# Main.net
KiCad netlist of a schematic drawn in Altium Designer
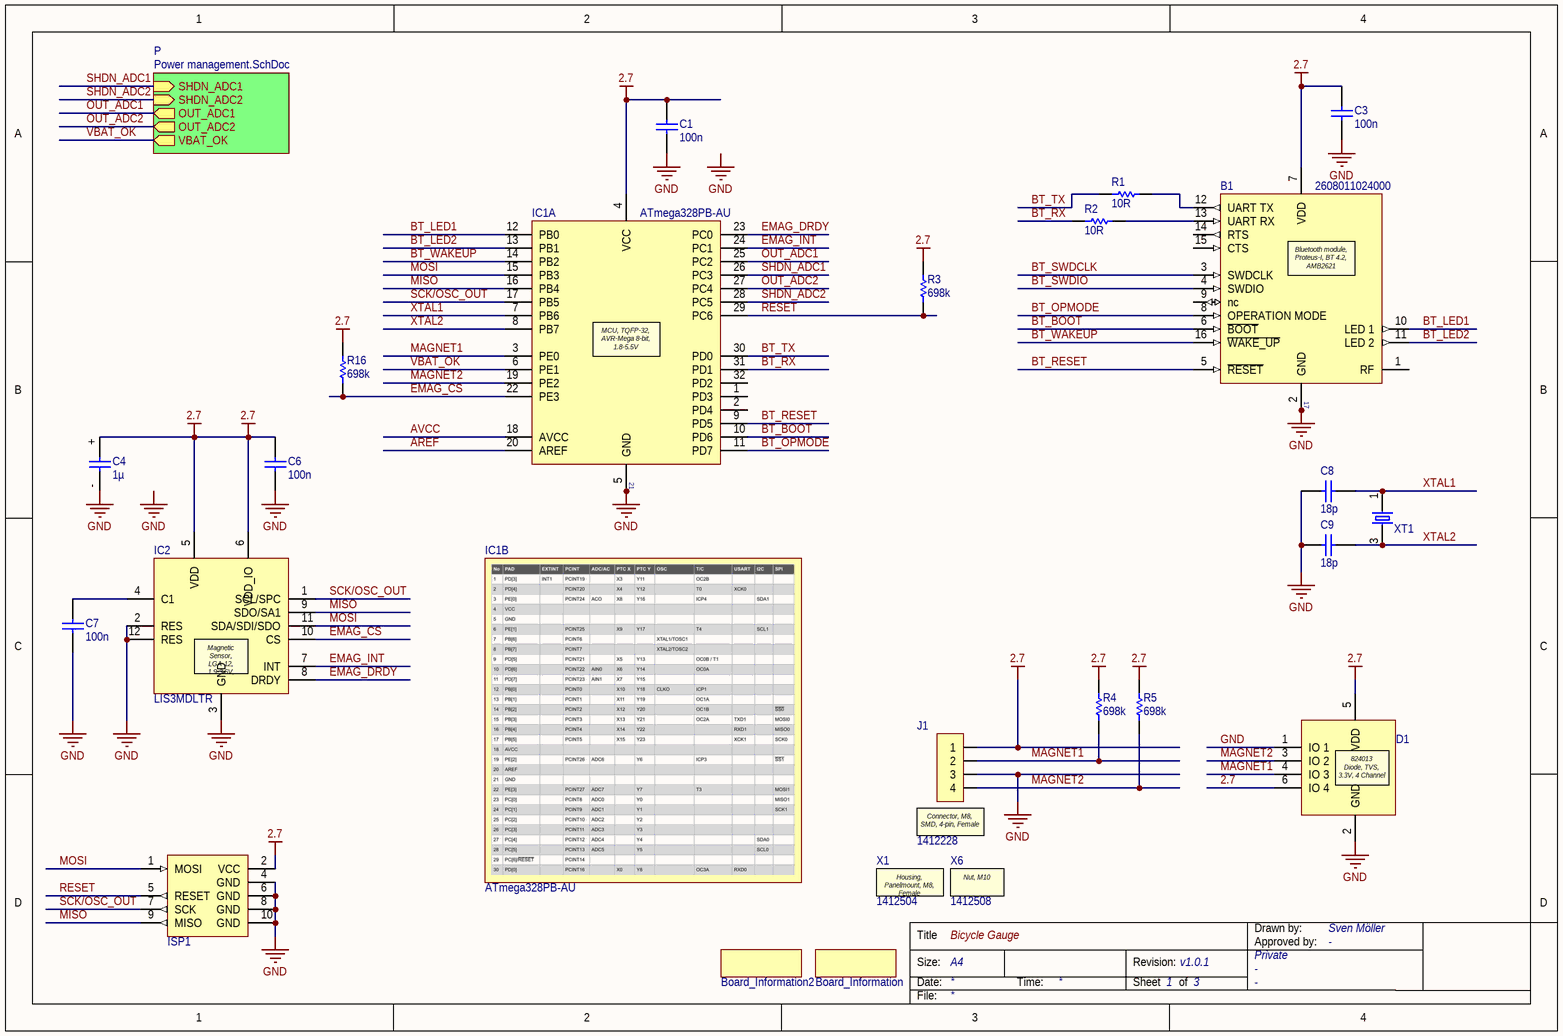
[diagram p0: Main.SchDoc]

(export (version "E")
  (design (tool "Eeschema 10.0.6"))
  (components
    (comp (ref "B1")
      (value "2608011024000")
      (footprint "AMB2621")
      (description "Bluetooth module, Proteus-I, BT 4.2, AMB2621")
      (fields (field (name "MANUFACTURER") "Würth Elektronik") (field (name "MPN") "2608011024000"))
      (libsource (lib "Schlib1") (part "2608011024000"))
    )
    (comp (ref "Board_Information")
      (value "Board_Information")
      (footprint "Board_Information")
      (description "Board Information")
      (libsource (lib "Schlib1") (part "Board_Information"))
    )
    (comp (ref "Board_Information2")
      (value "Board_Information")
      (footprint "Board_Information")
      (description "Board Information")
      (libsource (lib "Schlib1") (part "Board_Information"))
    )
    (comp (ref "C1")
      (value "100n")
      (footprint "C0603")
      (description "Cap, 100n, 0603, X7R, 50V")
      (fields (field (name "MANUFACTURER") "Yageo") (field (name "MPN") "CC0603KRX7R9BB104"))
      (libsource (lib "Createc Circuitstudio Library") (part "CC0603KRX7R9BB104"))
    )
    (comp (ref "C3")
      (value "100n")
      (footprint "C0603")
      (description "Cap, 100n, 0603, X7R, 50V")
      (fields (field (name "MANUFACTURER") "Yageo") (field (name "MPN") "CC0603KRX7R9BB104"))
      (libsource (lib "Createc Circuitstudio Library") (part "CC0603KRX7R9BB104"))
    )
    (comp (ref "C4")
      (value "1µ")
      (footprint "ELCAP_4x5.4mm")
      (description "Cap, 1µ, 4x5.4mm, Aluminum Electrolyte, 35V")
      (fields (field (name "MPN") "EEE-FC1V1R0R") (field (name "MANUFACTURER") "Panasonic"))
      (libsource (lib "Schlib1") (part "EEE-FC1V1R0R"))
    )
    (comp (ref "C6")
      (value "100n")
      (footprint "C0603")
      (description "Cap, 100n, 0603, X7R, 50V")
      (fields (field (name "MANUFACTURER") "Yageo") (field (name "MPN") "CC0603KRX7R9BB104"))
      (libsource (lib "Createc Circuitstudio Library") (part "CC0603KRX7R9BB104"))
    )
    (comp (ref "C7")
      (value "100n")
      (footprint "C0603")
      (description "Cap, 100n, 0603, X7R, 50V")
      (fields (field (name "MANUFACTURER") "Yageo") (field (name "MPN") "CC0603KRX7R9BB104"))
      (libsource (lib "Createc Circuitstudio Library") (part "CC0603KRX7R9BB104"))
    )
    (comp (ref "C8")
      (value "18p")
      (footprint "C0603")
      (description "Cap, 18p, 0603, C0G, 50V")
      (fields (field (name "MPN") "C0603C180J5GACTU") (field (name "MANUFACTURER") "Kemet"))
      (libsource (lib "Schlib1") (part "C0603C180J5GACTU"))
    )
    (comp (ref "C9")
      (value "18p")
      (footprint "C0603")
      (description "Cap, 18p, 0603, C0G, 50V")
      (fields (field (name "MPN") "C0603C180J5GACTU") (field (name "MANUFACTURER") "Kemet"))
      (libsource (lib "Schlib1") (part "C0603C180J5GACTU"))
    )
    (comp (ref "D1")
      (value "824013")
      (footprint "SOT-23-6")
      (description "Diode, TVS, 3.3V, 4 Channel")
      (fields (field (name "MANUFACTURER") "Würth Electronics"))
      (libsource (lib "Createc Circuitstudio Library") (part "824013"))
    )
    (comp (ref "IC1")
      (value "ATmega328PB-AU")
      (footprint "TQFP-32")
      (description "MCU, TQFP-32, AVR-Mega 8-bit, 1.8-5.5V")
      (fields (field (name "MANUFACTURER") "Microchip") (field (name "MPN") "ATmega328PB-AU"))
      (libsource (lib "Schlib1") (part "ATmega328PB-AU"))
    )
    (comp (ref "IC2")
      (value "LIS3MDLTR")
      (footprint "LGA-12")
      (description "Magnetic Sensor, LGA-12, 1.9-3.6V, +/-1.6mT")
      (fields (field (name "MANUFACTURER") "ST Microelectronics") (field (name "MPN") "LIS3MDLTR"))
      (libsource (lib "Schlib1") (part "LIS3MDLTR"))
    )
    (comp (ref "ISP1")
      (value "TC2050-IDC-NL")
      (footprint "TC2050-IDC-NL")
      (libsource (lib "Createc Circuitstudio Library") (part "TC2050-IDC-NL"))
    )
    (comp (ref "J1")
      (value "1412228")
      (footprint "1412228")
      (description "Connector, M8, SMD, 4-pin, Female")
      (fields (field (name "MANUFACTURER") "Phoenix Contact") (field (name "MPN") "1412228"))
      (libsource (lib "Schlib1") (part "1412228"))
    )
    (comp (ref "R1")
      (value "10R")
      (footprint "R0603")
      (description "Res, 10R, 0603, 1%, 100mW, 50V")
      (fields (field (name "TOLERANCE") "1%") (field (name "MPN") "ERJ-3EKF10R0V"))
      (libsource (lib "Createc Circuitstudio Library") (part "ERJ-3EKF10R0V"))
    )
    (comp (ref "R2")
      (value "10R")
      (footprint "R0603")
      (description "Res, 10R, 0603, 1%, 100mW, 50V")
      (fields (field (name "TOLERANCE") "1%") (field (name "MPN") "ERJ-3EKF10R0V"))
      (libsource (lib "Createc Circuitstudio Library") (part "ERJ-3EKF10R0V"))
    )
    (comp (ref "R3")
      (value "698k")
      (footprint "R0603")
      (description "Res, 698k, 0603, 1%, 75V, 100mW")
      (fields (field (name "TOLERANCE") "1%") (field (name "MPN") "ERJ-3EKF6983V"))
      (libsource (lib "Schlib1") (part "ERJ-3EKF6983V"))
    )
    (comp (ref "R4")
      (value "698k")
      (footprint "R0603")
      (description "Res, 698k, 0603, 1%, 75V, 100mW")
      (fields (field (name "TOLERANCE") "1%") (field (name "MPN") "ERJ-3EKF6983V"))
      (libsource (lib "Schlib1") (part "ERJ-3EKF6983V"))
    )
    (comp (ref "R5")
      (value "698k")
      (footprint "R0603")
      (description "Res, 698k, 0603, 1%, 75V, 100mW")
      (fields (field (name "TOLERANCE") "1%") (field (name "MPN") "ERJ-3EKF6983V"))
      (libsource (lib "Schlib1") (part "ERJ-3EKF6983V"))
    )
    (comp (ref "R16")
      (value "698k")
      (footprint "R0603")
      (description "Res, 698k, 0603, 1%, 75V, 100mW")
      (fields (field (name "TOLERANCE") "1%") (field (name "MPN") "ERJ-3EKF6983V"))
      (libsource (lib "Schlib1") (part "ERJ-3EKF6983V"))
    )
    (comp (ref "X1")
      (value "1412504")
      (footprint "1412504")
      (description "Housing, Panelmount, M8, Female")
      (fields (field (name "MANUFACTURER") "Phoenix Contact") (field (name "MPN") "1412504"))
      (libsource (lib "Schlib1") (part "1412504"))
    )
    (comp (ref "X6")
      (value "1412508")
      (footprint "1412508")
      (description "Nut, M10")
      (fields (field (name "MANUFACTURER") "Phoenix Contact") (field (name "MPN") "1412508"))
      (libsource (lib "Schlib1") (part "1412508"))
    )
    (comp (ref "XT1")
      (value "ABMM2-7.3728MHZ-E2-T")
      (footprint "Crystal_6x3.6mm")
      (description "Crystal, SMD, 7.3728MHz, 18pF")
      (fields (field (name "MANUFACTURER") "Abracon"))
      (libsource (lib "Schlib1") (part "ABMM2-7.3728MHZ-E2-T"))
    )
  )
  (nets
    (net (code "1") (name "/AREF") (class "Default")
      (node (ref "IC1") (pin "20") (pinfunction "AREF_20") (pintype "passive"))
    )
    (net (code "2") (name "/AVCC") (class "Default")
      (node (ref "IC1") (pin "18") (pinfunction "AVCC_18") (pintype "passive"))
    )
    (net (code "3") (name "/BT_BOOT") (class "Default")
      (node (ref "B1") (pin "6") (pinfunction "~{BOOT}_6") (pintype "input"))
      (node (ref "IC1") (pin "10") (pinfunction "PD6_10") (pintype "passive"))
    )
    (net (code "4") (name "/BT_LED1") (class "Default")
      (node (ref "B1") (pin "10") (pinfunction "LED_1_10") (pintype "output"))
      (node (ref "IC1") (pin "12") (pinfunction "PB0_12") (pintype "passive"))
    )
    (net (code "5") (name "/BT_LED2") (class "Default")
      (node (ref "B1") (pin "11") (pinfunction "LED_2_11") (pintype "output"))
      (node (ref "IC1") (pin "13") (pinfunction "PB1_13") (pintype "passive"))
    )
    (net (code "6") (name "/BT_OPMODE") (class "Default")
      (node (ref "B1") (pin "8") (pinfunction "OPERATION_MODE_8") (pintype "input"))
      (node (ref "IC1") (pin "11") (pinfunction "PD7_11") (pintype "passive"))
    )
    (net (code "7") (name "/BT_RESET") (class "Default")
      (node (ref "B1") (pin "5") (pinfunction "~{RESET}_5") (pintype "input"))
      (node (ref "IC1") (pin "9") (pinfunction "PD5_9") (pintype "passive"))
    )
    (net (code "8") (name "/BT_RX") (class "Default")
      (node (ref "IC1") (pin "31") (pinfunction "PD1_31") (pintype "passive"))
      (node (ref "R2") (pin "1") (pinfunction "1_1") (pintype "passive"))
    )
    (net (code "9") (name "/BT_SWDCLK") (class "Default")
      (node (ref "B1") (pin "3") (pinfunction "SWDCLK_3") (pintype "input"))
    )
    (net (code "10") (name "/BT_SWDIO") (class "Default")
      (node (ref "B1") (pin "4") (pinfunction "SWDIO_4") (pintype "input"))
    )
    (net (code "11") (name "/BT_TX") (class "Default")
      (node (ref "IC1") (pin "30") (pinfunction "PD0_30") (pintype "passive"))
      (node (ref "R1") (pin "1") (pinfunction "1_1") (pintype "passive"))
    )
    (net (code "12") (name "/BT_WAKEUP") (class "Default")
      (node (ref "B1") (pin "16") (pinfunction "~{WAKE_UP}_16") (pintype "input"))
      (node (ref "IC1") (pin "14") (pinfunction "PB2_14") (pintype "passive"))
    )
    (net (code "13") (name "/EMAG_CS") (class "Default")
      (node (ref "IC1") (pin "22") (pinfunction "PE3_22") (pintype "passive"))
      (node (ref "IC2") (pin "10") (pinfunction "CS_10") (pintype "passive"))
      (node (ref "R16") (pin "1") (pinfunction "1_1") (pintype "passive"))
    )
    (net (code "14") (name "/EMAG_DRDY") (class "Default")
      (node (ref "IC1") (pin "23") (pinfunction "PC0_23") (pintype "passive"))
      (node (ref "IC2") (pin "8") (pinfunction "DRDY_8") (pintype "passive"))
    )
    (net (code "15") (name "/EMAG_INT") (class "Default")
      (node (ref "IC1") (pin "24") (pinfunction "PC1_24") (pintype "passive"))
      (node (ref "IC2") (pin "7") (pinfunction "INT_7") (pintype "passive"))
    )
    (net (code "16") (name "/MAGNET1") (class "Default")
      (node (ref "D1") (pin "4") (pinfunction "IO_3_4") (pintype "passive"))
      (node (ref "IC1") (pin "3") (pinfunction "PE0_3") (pintype "passive"))
      (node (ref "J1") (pin "2") (pinfunction "2_2") (pintype "passive"))
      (node (ref "R4") (pin "1") (pinfunction "1_1") (pintype "passive"))
    )
    (net (code "17") (name "/MAGNET2") (class "Default")
      (node (ref "D1") (pin "3") (pinfunction "IO_2_3") (pintype "passive"))
      (node (ref "IC1") (pin "19") (pinfunction "PE2_19") (pintype "passive"))
      (node (ref "J1") (pin "4") (pinfunction "4_4") (pintype "passive"))
      (node (ref "R5") (pin "1") (pinfunction "1_1") (pintype "passive"))
    )
    (net (code "18") (name "/MISO") (class "Default")
      (node (ref "IC1") (pin "16") (pinfunction "PB4_16") (pintype "passive"))
      (node (ref "IC2") (pin "9") (pinfunction "SDO/SA1_9") (pintype "passive"))
      (node (ref "ISP1") (pin "9") (pinfunction "MISO_9") (pintype "output"))
    )
    (net (code "19") (name "/MOSI") (class "Default")
      (node (ref "IC1") (pin "15") (pinfunction "PB3_15") (pintype "passive"))
      (node (ref "IC2") (pin "11") (pinfunction "SDA/SDI/SDO_11") (pintype "passive"))
      (node (ref "ISP1") (pin "1") (pinfunction "MOSI_1") (pintype "input"))
    )
    (net (code "20") (name "/OUT_ADC1") (class "Default")
      (node (ref "IC1") (pin "25") (pinfunction "PC2_25") (pintype "passive"))
    )
    (net (code "21") (name "/OUT_ADC2") (class "Default")
      (node (ref "IC1") (pin "27") (pinfunction "PC4_27") (pintype "passive"))
    )
    (net (code "22") (name "/RESET") (class "Default")
      (node (ref "IC1") (pin "29") (pinfunction "PC6_29") (pintype "passive"))
      (node (ref "ISP1") (pin "5") (pinfunction "RESET_5") (pintype "output"))
      (node (ref "R3") (pin "1") (pinfunction "1_1") (pintype "passive"))
    )
    (net (code "23") (name "/SCK{slash}OSC_OUT") (class "Default")
      (node (ref "IC1") (pin "17") (pinfunction "PB5_17") (pintype "passive"))
      (node (ref "IC2") (pin "1") (pinfunction "SCL/SPC_1") (pintype "passive"))
      (node (ref "ISP1") (pin "7") (pinfunction "SCK_7") (pintype "output"))
    )
    (net (code "24") (name "/SHDN_ADC1") (class "Default")
      (node (ref "IC1") (pin "26") (pinfunction "PC3_26") (pintype "passive"))
    )
    (net (code "25") (name "/SHDN_ADC2") (class "Default")
      (node (ref "IC1") (pin "28") (pinfunction "PC5_28") (pintype "passive"))
    )
    (net (code "26") (name "/VBAT_OK") (class "Default")
      (node (ref "IC1") (pin "6") (pinfunction "PE1_6") (pintype "passive"))
    )
    (net (code "27") (name "/XTAL1") (class "Default")
      (node (ref "C8") (pin "2") (pinfunction "2_2") (pintype "passive"))
      (node (ref "IC1") (pin "7") (pinfunction "PB6_7") (pintype "passive"))
      (node (ref "XT1") (pin "1") (pinfunction "1_1") (pintype "passive"))
    )
    (net (code "28") (name "/XTAL2") (class "Default")
      (node (ref "C9") (pin "2") (pinfunction "2_2") (pintype "passive"))
      (node (ref "IC1") (pin "8") (pinfunction "PB7_8") (pintype "passive"))
      (node (ref "XT1") (pin "3") (pinfunction "3_3") (pintype "passive"))
    )
    (net (code "29") (name "2.7") (class "Default")
      (node (ref "B1") (pin "7") (pinfunction "VDD_7") (pintype "passive"))
      (node (ref "C1") (pin "2") (pinfunction "2_2") (pintype "passive"))
      (node (ref "C3") (pin "2") (pinfunction "2_2") (pintype "passive"))
      (node (ref "C4") (pin "+") (pinfunction "1_+") (pintype "passive"))
      (node (ref "C6") (pin "2") (pinfunction "2_2") (pintype "passive"))
      (node (ref "D1") (pin "5") (pinfunction "VDD_5") (pintype "passive"))
      (node (ref "D1") (pin "6") (pinfunction "IO_4_6") (pintype "passive"))
      (node (ref "IC1") (pin "4") (pinfunction "VCC_4") (pintype "passive"))
      (node (ref "IC2") (pin "5") (pinfunction "VDD_5") (pintype "passive"))
      (node (ref "IC2") (pin "6") (pinfunction "VDD_IO_6") (pintype "passive"))
      (node (ref "ISP1") (pin "2") (pinfunction "VCC_2") (pintype "power_in"))
      (node (ref "J1") (pin "1") (pinfunction "1_1") (pintype "passive"))
      (node (ref "R16") (pin "2") (pinfunction "2_2") (pintype "passive"))
      (node (ref "R3") (pin "2") (pinfunction "2_2") (pintype "passive"))
      (node (ref "R4") (pin "2") (pinfunction "2_2") (pintype "passive"))
      (node (ref "R5") (pin "2") (pinfunction "2_2") (pintype "passive"))
    )
    (net (code "30") (name "GND") (class "Default")
      (node (ref "B1") (pin "17") (pinfunction "GND_17") (pintype "passive"))
      (node (ref "B1") (pin "2") (pinfunction "GND_2") (pintype "passive"))
      (node (ref "C1") (pin "1") (pinfunction "1_1") (pintype "passive"))
      (node (ref "C3") (pin "1") (pinfunction "1_1") (pintype "passive"))
      (node (ref "C4") (pin "-") (pinfunction "2_-") (pintype "passive"))
      (node (ref "C6") (pin "1") (pinfunction "1_1") (pintype "passive"))
      (node (ref "C7") (pin "1") (pinfunction "1_1") (pintype "passive"))
      (node (ref "C8") (pin "1") (pinfunction "1_1") (pintype "passive"))
      (node (ref "C9") (pin "1") (pinfunction "1_1") (pintype "passive"))
      (node (ref "D1") (pin "1") (pinfunction "IO_1_1") (pintype "passive"))
      (node (ref "D1") (pin "2") (pinfunction "GND_2") (pintype "passive"))
      (node (ref "IC1") (pin "21") (pinfunction "GND_21") (pintype "passive"))
      (node (ref "IC1") (pin "5") (pinfunction "GND_5") (pintype "passive"))
      (node (ref "IC2") (pin "12") (pinfunction "RES_12") (pintype "passive"))
      (node (ref "IC2") (pin "2") (pinfunction "RES_2") (pintype "passive"))
      (node (ref "IC2") (pin "3") (pinfunction "GND_3") (pintype "passive"))
      (node (ref "ISP1") (pin "10") (pinfunction "GND_10") (pintype "passive"))
      (node (ref "ISP1") (pin "4") (pinfunction "GND_4") (pintype "passive"))
      (node (ref "ISP1") (pin "6") (pinfunction "GND_6") (pintype "passive"))
      (node (ref "ISP1") (pin "8") (pinfunction "GND_8") (pintype "passive"))
      (node (ref "J1") (pin "3") (pinfunction "3_3") (pintype "passive"))
    )
    (net (code "31") (name "Net-(B1-UART_RX)") (class "Default")
      (node (ref "B1") (pin "13") (pinfunction "UART_RX_13") (pintype "input"))
      (node (ref "R2") (pin "2") (pinfunction "2_2") (pintype "passive"))
    )
    (net (code "32") (name "Net-(B1-UART_TX)") (class "Default")
      (node (ref "B1") (pin "12") (pinfunction "UART_TX_12") (pintype "output"))
      (node (ref "R1") (pin "2") (pinfunction "2_2") (pintype "passive"))
    )
    (net (code "33") (name "Net-(IC2-C1)") (class "Default")
      (node (ref "C7") (pin "2") (pinfunction "2_2") (pintype "passive"))
      (node (ref "IC2") (pin "4") (pinfunction "C1_4") (pintype "passive"))
    )
    (net (code "34") (name "unconnected-(B1-CTS-Pad15)") (class "Default")
      (node (ref "B1") (pin "15") (pinfunction "CTS_15") (pintype "input"))
    )
    (net (code "35") (name "unconnected-(B1-RF-Pad1)") (class "Default")
      (node (ref "B1") (pin "1") (pinfunction "RF_1") (pintype "passive"))
    )
    (net (code "36") (name "unconnected-(B1-RTS-Pad14)") (class "Default")
      (node (ref "B1") (pin "14") (pinfunction "RTS_14") (pintype "output"))
    )
    (net (code "37") (name "unconnected-(B1-nc-Pad9)") (class "Default")
      (node (ref "B1") (pin "9") (pinfunction "nc_9") (pintype "bidirectional"))
    )
    (net (code "38") (name "unconnected-(IC1A-PD2-Pad32)") (class "Default")
      (node (ref "IC1") (pin "32") (pinfunction "PD2_32") (pintype "passive"))
    )
    (net (code "39") (name "unconnected-(IC1A-PD3-Pad1)") (class "Default")
      (node (ref "IC1") (pin "1") (pinfunction "PD3_1") (pintype "passive"))
    )
    (net (code "40") (name "unconnected-(IC1A-PD4-Pad2)") (class "Default")
      (node (ref "IC1") (pin "2") (pinfunction "PD4_2") (pintype "passive"))
    )
  )
)
